# Microcontroller.net
KiCad netlist of a schematic drawn in Altium Designer
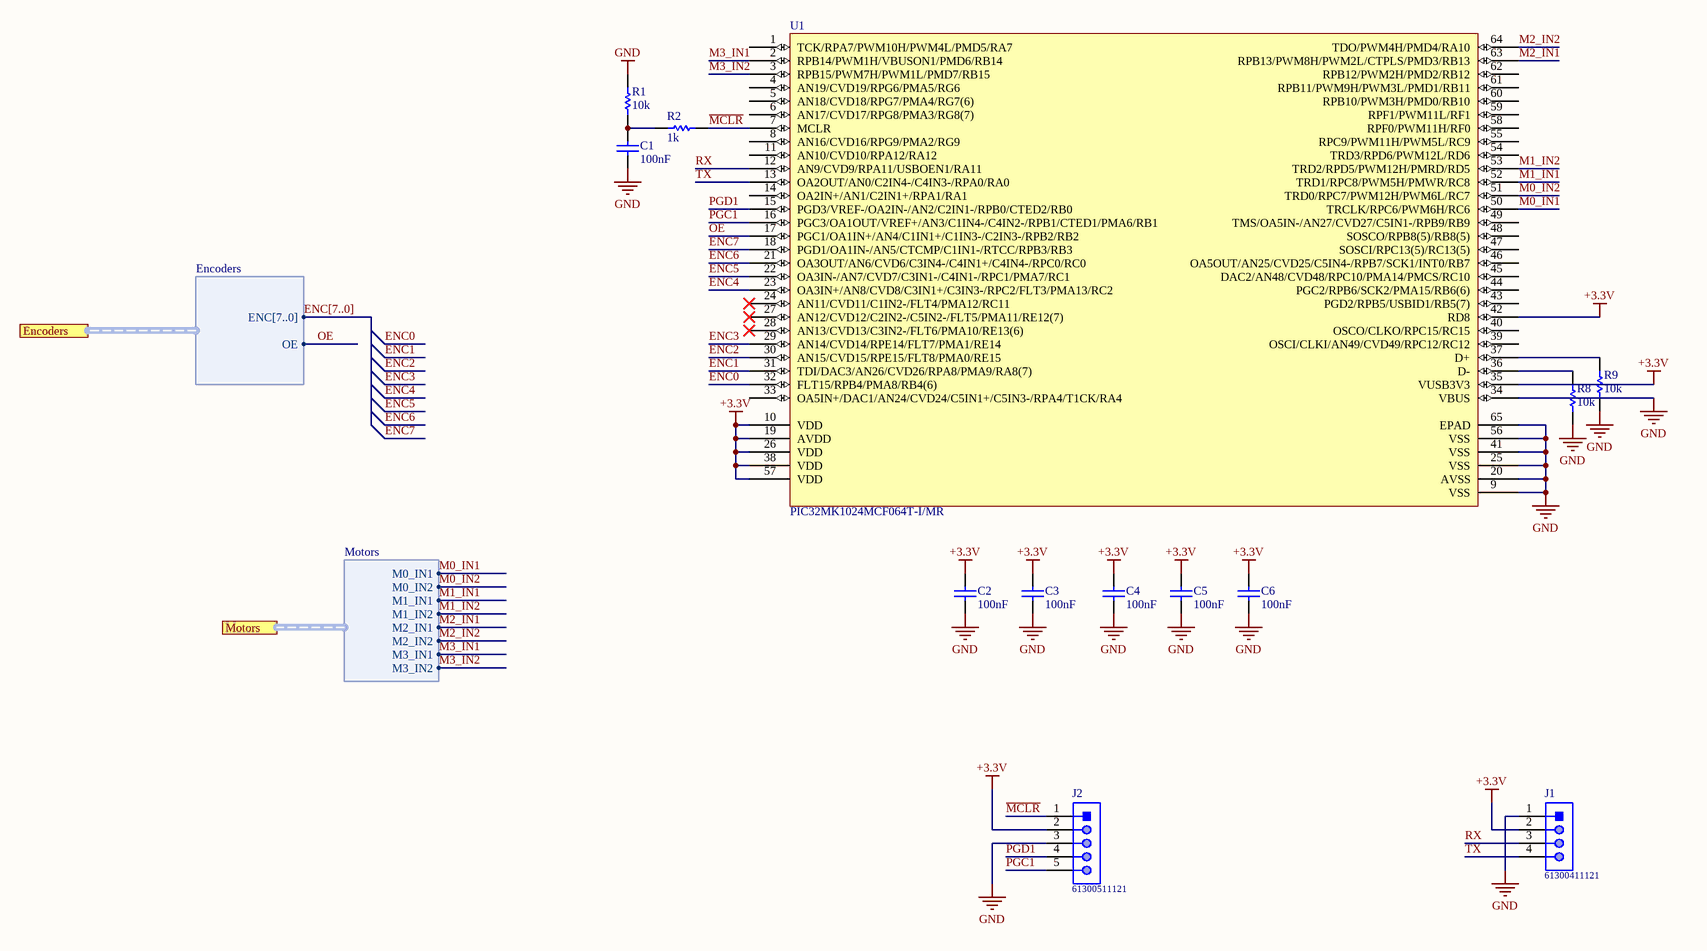
[diagram p0: Microcontroller.SchDoc]

(export (version "E")
  (design (tool "Eeschema 10.0.6"))
  (components
    (comp (ref "C1")
      (value "100nF")
      (footprint "0402")
      (description "TDK - C1005X7R1C104K050BC. - CERAMIC CAPACITOR, 0.1UF, 16V, X7R, 10%, 0402, FULL REEL")
      (fields
        (field (name "MANUFACTURER") "TDK")
        (field (name "MANUFACTURER PART NUMBER") "C1005X7R1C104K050BC")
      )
      (libsource (lib "altium-library") (part "Capacitor"))
    )
    (comp (ref "C2")
      (value "100nF")
      (footprint "0402")
      (description "TDK - C1005X7R1C104K050BC. - CERAMIC CAPACITOR, 0.1UF, 16V, X7R, 10%, 0402, FULL REEL")
      (fields
        (field (name "MANUFACTURER") "TDK")
        (field (name "MANUFACTURER PART NUMBER") "C1005X7R1C104K050BC")
      )
      (libsource (lib "altium-library") (part "Capacitor"))
    )
    (comp (ref "C3")
      (value "100nF")
      (footprint "0402")
      (description "TDK - C1005X7R1C104K050BC. - CERAMIC CAPACITOR, 0.1UF, 16V, X7R, 10%, 0402, FULL REEL")
      (fields
        (field (name "MANUFACTURER") "TDK")
        (field (name "MANUFACTURER PART NUMBER") "C1005X7R1C104K050BC")
      )
      (libsource (lib "altium-library") (part "Capacitor"))
    )
    (comp (ref "C4")
      (value "100nF")
      (footprint "0402")
      (description "TDK - C1005X7R1C104K050BC. - CERAMIC CAPACITOR, 0.1UF, 16V, X7R, 10%, 0402, FULL REEL")
      (fields
        (field (name "MANUFACTURER") "TDK")
        (field (name "MANUFACTURER PART NUMBER") "C1005X7R1C104K050BC")
      )
      (libsource (lib "altium-library") (part "Capacitor"))
    )
    (comp (ref "C5")
      (value "100nF")
      (footprint "0402")
      (description "TDK - C1005X7R1C104K050BC. - CERAMIC CAPACITOR, 0.1UF, 16V, X7R, 10%, 0402, FULL REEL")
      (fields
        (field (name "MANUFACTURER") "TDK")
        (field (name "MANUFACTURER PART NUMBER") "C1005X7R1C104K050BC")
      )
      (libsource (lib "altium-library") (part "Capacitor"))
    )
    (comp (ref "C6")
      (value "100nF")
      (footprint "0402")
      (description "TDK - C1005X7R1C104K050BC. - CERAMIC CAPACITOR, 0.1UF, 16V, X7R, 10%, 0402, FULL REEL")
      (fields
        (field (name "MANUFACTURER") "TDK")
        (field (name "MANUFACTURER PART NUMBER") "C1005X7R1C104K050BC")
      )
      (libsource (lib "altium-library") (part "Capacitor"))
    )
    (comp (ref "J1")
      (value "61300411121")
      (footprint "61300411121")
      (description "THT Vertical Pin Header WR-PHD, Pitch 2.54 mm, Single Row, 4 pins")
      (fields (field (name "MANUFACTURER") "Wurth Elektronik") (field (name "PUBLISHER") "WurthElektronik"))
      (libsource (lib "Altium Content Vault") (part "WE-CN-1P-M-R4"))
    )
    (comp (ref "J2")
      (value "61300511121")
      (footprint "61300511121")
      (description "THT Vertical Pin Header WR-PHD, Pitch 2.54 mm, Single Row, 5 pins")
      (fields (field (name "MANUFACTURER") "Wurth Elektronik") (field (name "PUBLISHER") "WurthElektronik"))
      (libsource (lib "Altium Content Vault") (part "WE-CN-1P-M-R5"))
    )
    (comp (ref "R1")
      (value "10k")
      (footprint "0402")
      (description "D10/CRCW0402-C 100 10K 1% ET7")
      (fields
        (field (name "MANUFACTURER") "Vishay")
        (field (name "MANUFACTURER PART NUMBER") "CRCW040210K0FKEDC")
      )
      (libsource (lib "altium-library") (part "Resistor"))
    )
    (comp (ref "R2")
      (value "1k")
      (footprint "0402")
      (description "Res Thick Film 0402 1K Ohm 1% 1/16W ±100ppm/°C Molded SMD Paper T/R")
      (fields
        (field (name "MANUFACTURER") "Vishay Dale")
        (field (name "MANUFACTURER PART NUMBER") "CRCW04021K00FKED")
      )
      (libsource (lib "altium-library") (part "Resistor"))
    )
    (comp (ref "R8")
      (value "10k")
      (footprint "0402")
      (description "D10/CRCW0402-C 100 10K 1% ET7")
      (fields
        (field (name "MANUFACTURER") "Vishay")
        (field (name "MANUFACTURER PART NUMBER") "CRCW040210K0FKEDC")
      )
      (libsource (lib "altium-library") (part "Resistor"))
    )
    (comp (ref "R9")
      (value "10k")
      (footprint "0402")
      (description "D10/CRCW0402-C 100 10K 1% ET7")
      (fields
        (field (name "MANUFACTURER") "Vishay")
        (field (name "MANUFACTURER PART NUMBER") "CRCW040210K0FKEDC")
      )
      (libsource (lib "altium-library") (part "Resistor"))
    )
    (comp (ref "U1")
      (value "PIC32MK1024MCF064T-I/MR")
      (footprint "64-TQFP")
      (description "IC MCU 32BIT 1MB FLASH 64TQFP")
      (fields
        (field (name "MANUFACTURER") "Microchip")
        (field (name "MANUFACTURER PART NUMBER") "PIC32MK1024MCF064-I/PT")
      )
      (libsource (lib "altium-library") (part "PIC32MK1024MCF064T-I/MR"))
    )
  )
  (nets
    (net (code "3") (name "+3.3V") (class "Default")
      (node (ref "C2") (pin "2") (pinfunction "2_2") (pintype "passive"))
      (node (ref "C3") (pin "2") (pinfunction "2_2") (pintype "passive"))
      (node (ref "C4") (pin "2") (pinfunction "2_2") (pintype "passive"))
      (node (ref "C5") (pin "2") (pinfunction "2_2") (pintype "passive"))
      (node (ref "C6") (pin "2") (pinfunction "2_2") (pintype "passive"))
      (node (ref "J1") (pin "2") (pinfunction "2_2") (pintype "passive"))
      (node (ref "J2") (pin "2") (pinfunction "2_2") (pintype "passive"))
      (node (ref "U1") (pin "10") (pinfunction "VDD_10") (pintype "power_in"))
      (node (ref "U1") (pin "19") (pinfunction "AVDD_19") (pintype "power_in"))
      (node (ref "U1") (pin "26") (pinfunction "VDD_26") (pintype "power_in"))
      (node (ref "U1") (pin "35") (pinfunction "VUSB3V3_35") (pintype "bidirectional"))
      (node (ref "U1") (pin "38") (pinfunction "VDD_38") (pintype "power_in"))
      (node (ref "U1") (pin "42") (pinfunction "RD8_42") (pintype "bidirectional"))
      (node (ref "U1") (pin "57") (pinfunction "VDD_57") (pintype "power_in"))
    )
    (net (code "4") (name "/ENC0") (class "Default")
      (node (ref "U1") (pin "32") (pinfunction "FLT15/RPB4/PMA8/RB4(6)_32") (pintype "bidirectional"))
    )
    (net (code "5") (name "/ENC1") (class "Default")
      (node (ref "U1") (pin "31") (pinfunction "TDI/DAC3/AN26/CVD26/RPA8/PMA9/RA8(7)_31") (pintype "bidirectional"))
    )
    (net (code "6") (name "/ENC2") (class "Default")
      (node (ref "U1") (pin "30") (pinfunction "AN15/CVD15/RPE15/FLT8/PMA0/RE15_30") (pintype "bidirectional"))
    )
    (net (code "7") (name "/ENC3") (class "Default")
      (node (ref "U1") (pin "29") (pinfunction "AN14/CVD14/RPE14/FLT7/PMA1/RE14_29") (pintype "bidirectional"))
    )
    (net (code "8") (name "/ENC4") (class "Default")
      (node (ref "U1") (pin "23") (pinfunction "OA3IN+/AN8/CVD8/C3IN1+/C3IN3-/RPC2/FLT3/PMA13/RC2_23") (pintype "bidirectional"))
    )
    (net (code "9") (name "/ENC5") (class "Default")
      (node (ref "U1") (pin "22") (pinfunction "OA3IN-/AN7/CVD7/C3IN1-/C4IN1-/RPC1/PMA7/RC1_22") (pintype "bidirectional"))
    )
    (net (code "10") (name "/ENC6") (class "Default")
      (node (ref "U1") (pin "21") (pinfunction "OA3OUT/AN6/CVD6/C3IN4-/C4IN1+/C4IN4-/RPC0/RC0_21") (pintype "bidirectional"))
    )
    (net (code "11") (name "/ENC7") (class "Default")
      (node (ref "U1") (pin "18") (pinfunction "PGD1/OA1IN-/AN5/CTCMP/C1IN1-/RTCC/RPB3/RB3_18") (pintype "bidirectional"))
    )
    (net (code "13") (name "/M0_IN1") (class "Default")
      (node (ref "U1") (pin "50") (pinfunction "TRCLK/RPC6/PWM6H/RC6_50") (pintype "bidirectional"))
    )
    (net (code "14") (name "/M0_IN2") (class "Default")
      (node (ref "U1") (pin "51") (pinfunction "TRD0/RPC7/PWM12H/PWM6L/RC7_51") (pintype "bidirectional"))
    )
    (net (code "15") (name "/M1_IN1") (class "Default")
      (node (ref "U1") (pin "52") (pinfunction "TRD1/RPC8/PWM5H/PMWR/RC8_52") (pintype "bidirectional"))
    )
    (net (code "16") (name "/M1_IN2") (class "Default")
      (node (ref "U1") (pin "53") (pinfunction "TRD2/RPD5/PWM12H/PMRD/RD5_53") (pintype "bidirectional"))
    )
    (net (code "17") (name "/M2_IN1") (class "Default")
      (node (ref "U1") (pin "63") (pinfunction "RPB13/PWM8H/PWM2L/CTPLS/PMD3/RB13_63") (pintype "bidirectional"))
    )
    (net (code "18") (name "/M2_IN2") (class "Default")
      (node (ref "U1") (pin "64") (pinfunction "TDO/PWM4H/PMD4/RA10_64") (pintype "bidirectional"))
    )
    (net (code "19") (name "/M3_IN1") (class "Default")
      (node (ref "U1") (pin "2") (pinfunction "RPB14/PWM1H/VBUSON1/PMD6/RB14_2") (pintype "bidirectional"))
    )
    (net (code "20") (name "/M3_IN2") (class "Default")
      (node (ref "U1") (pin "3") (pinfunction "RPB15/PWM7H/PWM1L/PMD7/RB15_3") (pintype "bidirectional"))
    )
    (net (code "21") (name "/OE") (class "Default")
      (node (ref "U1") (pin "17") (pinfunction "PGC1/OA1IN+/AN4/C1IN1+/C1IN3-/C2IN3-/RPB2/RB2_17") (pintype "bidirectional"))
    )
    (net (code "22") (name "/PGC1") (class "Default")
      (node (ref "J2") (pin "5") (pinfunction "5_5") (pintype "passive"))
      (node (ref "U1") (pin "16") (pinfunction "PGC3/OA1OUT/VREF+/AN3/C1IN4-/C4IN2-/RPB1/CTED1/PMA6/RB1_16") (pintype "bidirectional"))
    )
    (net (code "23") (name "/PGD1") (class "Default")
      (node (ref "J2") (pin "4") (pinfunction "4_4") (pintype "passive"))
      (node (ref "U1") (pin "15") (pinfunction "PGD3/VREF-/OA2IN-/AN2/C2IN1-/RPB0/CTED2/RB0_15") (pintype "bidirectional"))
    )
    (net (code "24") (name "/RX") (class "Default")
      (node (ref "J1") (pin "3") (pinfunction "3_3") (pintype "passive"))
      (node (ref "U1") (pin "12") (pinfunction "AN9/CVD9/RPA11/USBOEN1/RA11_12") (pintype "bidirectional"))
    )
    (net (code "25") (name "/TX") (class "Default")
      (node (ref "J1") (pin "4") (pinfunction "4_4") (pintype "passive"))
      (node (ref "U1") (pin "13") (pinfunction "OA2OUT/AN0/C2IN4-/C4IN3-/RPA0/RA0_13") (pintype "bidirectional"))
    )
    (net (code "28") (name "/~{MCLR}") (class "Default")
      (node (ref "J2") (pin "1") (pinfunction "1_1") (pintype "passive"))
      (node (ref "R2") (pin "2") (pinfunction "2_2") (pintype "passive"))
      (node (ref "U1") (pin "7") (pinfunction "MCLR_7") (pintype "bidirectional"))
    )
    (net (code "29") (name "GND") (class "Default")
      (node (ref "C1") (pin "1") (pinfunction "1_1") (pintype "passive"))
      (node (ref "C2") (pin "1") (pinfunction "1_1") (pintype "passive"))
      (node (ref "C3") (pin "1") (pinfunction "1_1") (pintype "passive"))
      (node (ref "C4") (pin "1") (pinfunction "1_1") (pintype "passive"))
      (node (ref "C5") (pin "1") (pinfunction "1_1") (pintype "passive"))
      (node (ref "C6") (pin "1") (pinfunction "1_1") (pintype "passive"))
      (node (ref "J1") (pin "1") (pinfunction "1_1") (pintype "passive"))
      (node (ref "J2") (pin "3") (pinfunction "3_3") (pintype "passive"))
      (node (ref "R1") (pin "2") (pinfunction "2_2") (pintype "passive"))
      (node (ref "R8") (pin "1") (pinfunction "1_1") (pintype "passive"))
      (node (ref "R9") (pin "1") (pinfunction "1_1") (pintype "passive"))
      (node (ref "U1") (pin "20") (pinfunction "AVSS_20") (pintype "power_in"))
      (node (ref "U1") (pin "25") (pinfunction "VSS_25") (pintype "power_in"))
      (node (ref "U1") (pin "34") (pinfunction "VBUS_34") (pintype "bidirectional"))
      (node (ref "U1") (pin "41") (pinfunction "VSS_41") (pintype "power_in"))
      (node (ref "U1") (pin "56") (pinfunction "VSS_56") (pintype "power_in"))
      (node (ref "U1") (pin "65") (pinfunction "EPAD_65") (pintype "power_in"))
      (node (ref "U1") (pin "9") (pinfunction "VSS_9") (pintype "power_in"))
    )
    (net (code "30") (name "Net-(C1-Pad2)") (class "Default")
      (node (ref "C1") (pin "2") (pinfunction "2_2") (pintype "passive"))
      (node (ref "R1") (pin "1") (pinfunction "1_1") (pintype "passive"))
      (node (ref "R2") (pin "1") (pinfunction "1_1") (pintype "passive"))
    )
    (net (code "31") (name "Net-(U1-D+)") (class "Default")
      (node (ref "R9") (pin "2") (pinfunction "2_2") (pintype "passive"))
      (node (ref "U1") (pin "37") (pinfunction "D+_37") (pintype "bidirectional"))
    )
    (net (code "32") (name "Net-(U1-D-)") (class "Default")
      (node (ref "R8") (pin "2") (pinfunction "2_2") (pintype "passive"))
      (node (ref "U1") (pin "36") (pinfunction "D-_36") (pintype "bidirectional"))
    )
    (net (code "33") (name "unconnected-(U1-AN10{slash}CVD10{slash}RPA12{slash}RA12-Pad11)") (class "Default")
      (node (ref "U1") (pin "11") (pinfunction "AN10/CVD10/RPA12/RA12_11") (pintype "bidirectional"))
    )
    (net (code "34") (name "unconnected-(U1-AN11{slash}CVD11{slash}C1IN2-{slash}FLT4{slash}PMA12{slash}RC11-Pad24)") (class "Default")
      (node (ref "U1") (pin "24") (pinfunction "AN11/CVD11/C1IN2-/FLT4/PMA12/RC11_24") (pintype "bidirectional+no_connect"))
    )
    (net (code "35") (name "unconnected-(U1-AN12{slash}CVD12{slash}C2IN2-{slash}C5IN2-{slash}FLT5{slash}PMA11{slash}RE12(7)-Pad27)") (class "Default")
      (node (ref "U1") (pin "27") (pinfunction "AN12/CVD12/C2IN2-/C5IN2-/FLT5/PMA11/RE12(7)_27") (pintype "bidirectional+no_connect"))
    )
    (net (code "36") (name "unconnected-(U1-AN13{slash}CVD13{slash}C3IN2-{slash}FLT6{slash}PMA10{slash}RE13(6)-Pad28)") (class "Default")
      (node (ref "U1") (pin "28") (pinfunction "AN13/CVD13/C3IN2-/FLT6/PMA10/RE13(6)_28") (pintype "bidirectional+no_connect"))
    )
    (net (code "37") (name "unconnected-(U1-AN16{slash}CVD16{slash}RPG9{slash}PMA2{slash}RG9-Pad8)") (class "Default")
      (node (ref "U1") (pin "8") (pinfunction "AN16/CVD16/RPG9/PMA2/RG9_8") (pintype "bidirectional"))
    )
    (net (code "38") (name "unconnected-(U1-AN17{slash}CVD17{slash}RPG8{slash}PMA3{slash}RG8(7)-Pad6)") (class "Default")
      (node (ref "U1") (pin "6") (pinfunction "AN17/CVD17/RPG8/PMA3/RG8(7)_6") (pintype "bidirectional"))
    )
    (net (code "39") (name "unconnected-(U1-AN18{slash}CVD18{slash}RPG7{slash}PMA4{slash}RG7(6)-Pad5)") (class "Default")
      (node (ref "U1") (pin "5") (pinfunction "AN18/CVD18/RPG7/PMA4/RG7(6)_5") (pintype "bidirectional"))
    )
    (net (code "40") (name "unconnected-(U1-AN19{slash}CVD19{slash}RPG6{slash}PMA5{slash}RG6-Pad4)") (class "Default")
      (node (ref "U1") (pin "4") (pinfunction "AN19/CVD19/RPG6/PMA5/RG6_4") (pintype "bidirectional"))
    )
    (net (code "41") (name "unconnected-(U1-DAC2{slash}AN48{slash}CVD48{slash}RPC10{slash}PMA14{slash}PMCS{slash}RC10-Pad45)") (class "Default")
      (node (ref "U1") (pin "45") (pinfunction "DAC2/AN48/CVD48/RPC10/PMA14/PMCS/RC10_45") (pintype "bidirectional"))
    )
    (net (code "42") (name "unconnected-(U1-OA2IN+{slash}AN1{slash}C2IN1+{slash}RPA1{slash}RA1-Pad14)") (class "Default")
      (node (ref "U1") (pin "14") (pinfunction "OA2IN+/AN1/C2IN1+/RPA1/RA1_14") (pintype "bidirectional"))
    )
    (net (code "43") (name "unconnected-(U1-OA5IN+{slash}DAC1{slash}AN24{slash}CVD24{slash}C5IN1+{slash}C5IN3-{slash}RPA4{slash}T1CK{slash}RA4-Pad33)") (class "Default")
      (node (ref "U1") (pin "33") (pinfunction "OA5IN+/DAC1/AN24/CVD24/C5IN1+/C5IN3-/RPA4/T1CK/RA4_33") (pintype "bidirectional"))
    )
    (net (code "44") (name "unconnected-(U1-OA5OUT{slash}AN25{slash}CVD25{slash}C5IN4-{slash}RPB7{slash}SCK1{slash}INT0{slash}RB7-Pad46)") (class "Default")
      (node (ref "U1") (pin "46") (pinfunction "OA5OUT/AN25/CVD25/C5IN4-/RPB7/SCK1/INT0/RB7_46") (pintype "bidirectional"))
    )
    (net (code "45") (name "unconnected-(U1-OSCI{slash}CLKI{slash}AN49{slash}CVD49{slash}RPC12{slash}RC12-Pad39)") (class "Default")
      (node (ref "U1") (pin "39") (pinfunction "OSCI/CLKI/AN49/CVD49/RPC12/RC12_39") (pintype "bidirectional"))
    )
    (net (code "46") (name "unconnected-(U1-OSCO{slash}CLKO{slash}RPC15{slash}RC15-Pad40)") (class "Default")
      (node (ref "U1") (pin "40") (pinfunction "OSCO/CLKO/RPC15/RC15_40") (pintype "bidirectional"))
    )
    (net (code "47") (name "unconnected-(U1-PGC2{slash}RPB6{slash}SCK2{slash}PMA15{slash}RB6(6)-Pad44)") (class "Default")
      (node (ref "U1") (pin "44") (pinfunction "PGC2/RPB6/SCK2/PMA15/RB6(6)_44") (pintype "bidirectional"))
    )
    (net (code "48") (name "unconnected-(U1-PGD2{slash}RPB5{slash}USBID1{slash}RB5(7)-Pad43)") (class "Default")
      (node (ref "U1") (pin "43") (pinfunction "PGD2/RPB5/USBID1/RB5(7)_43") (pintype "bidirectional"))
    )
    (net (code "49") (name "unconnected-(U1-RPB10{slash}PWM3H{slash}PMD0{slash}RB10-Pad60)") (class "Default")
      (node (ref "U1") (pin "60") (pinfunction "RPB10/PWM3H/PMD0/RB10_60") (pintype "bidirectional"))
    )
    (net (code "50") (name "unconnected-(U1-RPB11{slash}PWM9H{slash}PWM3L{slash}PMD1{slash}RB11-Pad61)") (class "Default")
      (node (ref "U1") (pin "61") (pinfunction "RPB11/PWM9H/PWM3L/PMD1/RB11_61") (pintype "bidirectional"))
    )
    (net (code "51") (name "unconnected-(U1-RPB12{slash}PWM2H{slash}PMD2{slash}RB12-Pad62)") (class "Default")
      (node (ref "U1") (pin "62") (pinfunction "RPB12/PWM2H/PMD2/RB12_62") (pintype "bidirectional"))
    )
    (net (code "52") (name "unconnected-(U1-RPC9{slash}PWM11H{slash}PWM5L{slash}RC9-Pad55)") (class "Default")
      (node (ref "U1") (pin "55") (pinfunction "RPC9/PWM11H/PWM5L/RC9_55") (pintype "bidirectional"))
    )
    (net (code "53") (name "unconnected-(U1-RPF0{slash}PWM11H{slash}RF0-Pad58)") (class "Default")
      (node (ref "U1") (pin "58") (pinfunction "RPF0/PWM11H/RF0_58") (pintype "bidirectional"))
    )
    (net (code "54") (name "unconnected-(U1-RPF1{slash}PWM11L{slash}RF1-Pad59)") (class "Default")
      (node (ref "U1") (pin "59") (pinfunction "RPF1/PWM11L/RF1_59") (pintype "bidirectional"))
    )
    (net (code "55") (name "unconnected-(U1-SOSCI{slash}RPC13(5){slash}RC13(5)-Pad47)") (class "Default")
      (node (ref "U1") (pin "47") (pinfunction "SOSCI/RPC13(5)/RC13(5)_47") (pintype "bidirectional"))
    )
    (net (code "56") (name "unconnected-(U1-SOSCO{slash}RPB8(5){slash}RB8(5)-Pad48)") (class "Default")
      (node (ref "U1") (pin "48") (pinfunction "SOSCO/RPB8(5)/RB8(5)_48") (pintype "bidirectional"))
    )
    (net (code "57") (name "unconnected-(U1-TCK{slash}RPA7{slash}PWM10H{slash}PWM4L{slash}PMD5{slash}RA7-Pad1)") (class "Default")
      (node (ref "U1") (pin "1") (pinfunction "TCK/RPA7/PWM10H/PWM4L/PMD5/RA7_1") (pintype "bidirectional"))
    )
    (net (code "58") (name "unconnected-(U1-TMS{slash}OA5IN-{slash}AN27{slash}CVD27{slash}C5IN1-{slash}RPB9{slash}RB9-Pad49)") (class "Default")
      (node (ref "U1") (pin "49") (pinfunction "TMS/OA5IN-/AN27/CVD27/C5IN1-/RPB9/RB9_49") (pintype "bidirectional"))
    )
    (net (code "59") (name "unconnected-(U1-TRD3{slash}RPD6{slash}PWM12L{slash}RD6-Pad54)") (class "Default")
      (node (ref "U1") (pin "54") (pinfunction "TRD3/RPD6/PWM12L/RD6_54") (pintype "bidirectional"))
    )
  )
)
